# 1_esp32.net
KiCad netlist of a schematic drawn in Altium Designer
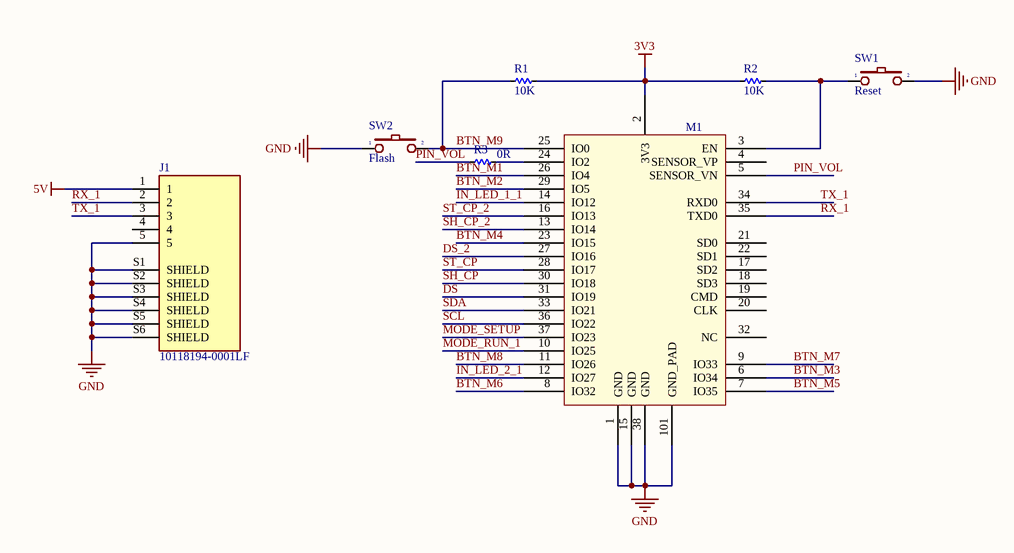
[diagram p0: [1]esp32.SchDoc]

(export (version "E")
  (design (tool "Eeschema 10.0.6"))
  (components
    (comp (ref "J1")
      (value "10118194-0001LF")
      (footprint "AMPHENOL_10118194-0001LF")
      (description "USB - micro B USB 2.0 Receptacle Connector 5 Position Surface Mount, Right Angle; Through Hole")
      (fields (field (name "MF") "Amphenol ICC"))
      (libsource (lib "10118194-0001LF") (part "10118194-0001LF"))
    )
    (comp (ref "M1")
      (value "ESP32S_Module")
      (footprint "ESP32S")
      (description "Esp-32S")
      (libsource (lib "ESP32S") (part "ESP32S_Module"))
    )
    (comp (ref "R1")
      (value "10K")
      (footprint "RES-SMD-0603")
      (description "Resistor")
      (fields
        (field (name "MANUFACTURER") "Generic Components")
        (field (name "PUBLISHER") "Altium Hobart Technology Centre")
      )
      (libsource (lib "LIBRARY") (part "Res-SMD"))
    )
    (comp (ref "R2")
      (value "10K")
      (footprint "RES-SMD-0603")
      (description "Resistor")
      (fields
        (field (name "MANUFACTURER") "Generic Components")
        (field (name "PUBLISHER") "Altium Hobart Technology Centre")
      )
      (libsource (lib "LIBRARY") (part "Res-SMD"))
    )
    (comp (ref "R3")
      (value "0R")
      (footprint "RES-SMD-0603")
      (description "Resistor")
      (fields
        (field (name "MANUFACTURER") "Generic Components")
        (field (name "PUBLISHER") "Altium Hobart Technology Centre")
      )
      (libsource (lib "LIBRARY") (part "Res-SMD"))
    )
    (comp (ref "SW1")
      (value "Reset")
      (footprint "SW1-SMD")
      (description "Switch button 2 pin")
      (libsource (lib "LIBRARY") (part "SW2"))
    )
    (comp (ref "SW2")
      (value "Flash")
      (footprint "SW-DIP1-1")
      (description "Switch button 2 pin")
      (libsource (lib "LIBRARY") (part "SW2"))
    )
  )
  (nets
    (net (code "1") (name "/BTN_M1") (class "Default")
      (node (ref "M1") (pin "26") (pinfunction "IO4_26") (pintype "passive"))
    )
    (net (code "2") (name "/BTN_M2") (class "Default")
      (node (ref "M1") (pin "29") (pinfunction "IO5_29") (pintype "passive"))
    )
    (net (code "3") (name "/BTN_M3") (class "Default")
      (node (ref "M1") (pin "6") (pinfunction "IO34_6") (pintype "passive"))
    )
    (net (code "4") (name "/BTN_M4") (class "Default")
      (node (ref "M1") (pin "23") (pinfunction "IO15_23") (pintype "passive"))
    )
    (net (code "5") (name "/BTN_M5") (class "Default")
      (node (ref "M1") (pin "7") (pinfunction "IO35_7") (pintype "passive"))
    )
    (net (code "6") (name "/BTN_M6") (class "Default")
      (node (ref "M1") (pin "8") (pinfunction "IO32_8") (pintype "passive"))
    )
    (net (code "7") (name "/BTN_M7") (class "Default")
      (node (ref "M1") (pin "9") (pinfunction "IO33_9") (pintype "passive"))
    )
    (net (code "8") (name "/BTN_M8") (class "Default")
      (node (ref "M1") (pin "11") (pinfunction "IO26_11") (pintype "passive"))
    )
    (net (code "9") (name "/BTN_M9") (class "Default")
      (node (ref "M1") (pin "25") (pinfunction "IO0_25") (pintype "passive"))
      (node (ref "R1") (pin "2") (pinfunction "2_2") (pintype "passive"))
      (node (ref "SW2") (pin "2") (pinfunction "2_2") (pintype "passive"))
    )
    (net (code "10") (name "/DS") (class "Default")
      (node (ref "M1") (pin "31") (pinfunction "IO19_31") (pintype "passive"))
    )
    (net (code "11") (name "/DS_2") (class "Default")
      (node (ref "M1") (pin "27") (pinfunction "IO16_27") (pintype "passive"))
    )
    (net (code "12") (name "/IN_LED_1_1") (class "Default")
      (node (ref "M1") (pin "14") (pinfunction "IO12_14") (pintype "passive"))
    )
    (net (code "13") (name "/IN_LED_2_1") (class "Default")
      (node (ref "M1") (pin "12") (pinfunction "IO27_12") (pintype "passive"))
    )
    (net (code "14") (name "/MODE_RUN_1") (class "Default")
      (node (ref "M1") (pin "10") (pinfunction "IO25_10") (pintype "passive"))
    )
    (net (code "15") (name "/MODE_SETUP") (class "Default")
      (node (ref "M1") (pin "37") (pinfunction "IO23_37") (pintype "passive"))
    )
    (net (code "16") (name "/PIN_VOL") (class "Default")
      (node (ref "M1") (pin "5") (pinfunction "SENSOR_VN_5") (pintype "passive"))
      (node (ref "R3") (pin "1") (pinfunction "1_1") (pintype "passive"))
    )
    (net (code "17") (name "/RX_1") (class "Default")
      (node (ref "J1") (pin "2") (pinfunction "2_2") (pintype "passive"))
      (node (ref "M1") (pin "35") (pinfunction "TXD0_35") (pintype "passive"))
    )
    (net (code "18") (name "/SCL") (class "Default")
      (node (ref "M1") (pin "36") (pinfunction "IO22_36") (pintype "passive"))
    )
    (net (code "19") (name "/SDA") (class "Default")
      (node (ref "M1") (pin "33") (pinfunction "IO21_33") (pintype "passive"))
    )
    (net (code "20") (name "/SH_CP") (class "Default")
      (node (ref "M1") (pin "30") (pinfunction "IO18_30") (pintype "passive"))
    )
    (net (code "21") (name "/SH_CP_2") (class "Default")
      (node (ref "M1") (pin "13") (pinfunction "IO14_13") (pintype "passive"))
    )
    (net (code "22") (name "/ST_CP") (class "Default")
      (node (ref "M1") (pin "28") (pinfunction "IO17_28") (pintype "passive"))
    )
    (net (code "23") (name "/ST_CP_2") (class "Default")
      (node (ref "M1") (pin "16") (pinfunction "IO13_16") (pintype "passive"))
    )
    (net (code "24") (name "/TX_1") (class "Default")
      (node (ref "J1") (pin "3") (pinfunction "3_3") (pintype "passive"))
      (node (ref "M1") (pin "34") (pinfunction "RXD0_34") (pintype "passive"))
    )
    (net (code "25") (name "3V3") (class "Default")
      (node (ref "M1") (pin "2") (pinfunction "3V3_2") (pintype "power_in"))
      (node (ref "R1") (pin "1") (pinfunction "1_1") (pintype "passive"))
      (node (ref "R2") (pin "2") (pinfunction "2_2") (pintype "passive"))
    )
    (net (code "26") (name "5V") (class "Default")
      (node (ref "J1") (pin "1") (pinfunction "1_1") (pintype "passive"))
    )
    (net (code "27") (name "GND") (class "Default")
      (node (ref "J1") (pin "5") (pinfunction "5_5") (pintype "passive"))
      (node (ref "J1") (pin "S1") (pinfunction "SHIELD_S1") (pintype "passive"))
      (node (ref "J1") (pin "S2") (pinfunction "SHIELD_S2") (pintype "passive"))
      (node (ref "J1") (pin "S3") (pinfunction "SHIELD_S3") (pintype "passive"))
      (node (ref "J1") (pin "S4") (pinfunction "SHIELD_S4") (pintype "passive"))
      (node (ref "J1") (pin "S5") (pinfunction "SHIELD_S5") (pintype "passive"))
      (node (ref "J1") (pin "S6") (pinfunction "SHIELD_S6") (pintype "passive"))
      (node (ref "M1") (pin "1") (pinfunction "GND_1") (pintype "power_in"))
      (node (ref "M1") (pin "101") (pinfunction "GND_PAD_101") (pintype "power_in"))
      (node (ref "M1") (pin "15") (pinfunction "GND_15") (pintype "power_in"))
      (node (ref "M1") (pin "38") (pinfunction "GND_38") (pintype "power_in"))
      (node (ref "SW1") (pin "2") (pinfunction "2_2") (pintype "passive"))
      (node (ref "SW2") (pin "1") (pinfunction "1_1") (pintype "passive"))
    )
    (net (code "28") (name "Net-(M1-EN)") (class "Default")
      (node (ref "M1") (pin "3") (pinfunction "EN_3") (pintype "power_in"))
      (node (ref "R2") (pin "1") (pinfunction "1_1") (pintype "passive"))
      (node (ref "SW1") (pin "1") (pinfunction "1_1") (pintype "passive"))
    )
    (net (code "29") (name "Net-(M1-IO2)") (class "Default")
      (node (ref "M1") (pin "24") (pinfunction "IO2_24") (pintype "passive"))
      (node (ref "R3") (pin "2") (pinfunction "2_2") (pintype "passive"))
    )
    (net (code "30") (name "unconnected-(J1-Pad4)") (class "Default")
      (node (ref "J1") (pin "4") (pinfunction "4_4") (pintype "passive"))
    )
    (net (code "31") (name "unconnected-(M1-CLK-Pad20)") (class "Default")
      (node (ref "M1") (pin "20") (pinfunction "CLK_20") (pintype "passive"))
    )
    (net (code "32") (name "unconnected-(M1-CMD-Pad19)") (class "Default")
      (node (ref "M1") (pin "19") (pinfunction "CMD_19") (pintype "passive"))
    )
    (net (code "33") (name "unconnected-(M1-NC-Pad32)") (class "Default")
      (node (ref "M1") (pin "32") (pinfunction "NC_32") (pintype "passive"))
    )
    (net (code "34") (name "unconnected-(M1-SD0-Pad21)") (class "Default")
      (node (ref "M1") (pin "21") (pinfunction "SD0_21") (pintype "passive"))
    )
    (net (code "35") (name "unconnected-(M1-SD1-Pad22)") (class "Default")
      (node (ref "M1") (pin "22") (pinfunction "SD1_22") (pintype "passive"))
    )
    (net (code "36") (name "unconnected-(M1-SD2-Pad17)") (class "Default")
      (node (ref "M1") (pin "17") (pinfunction "SD2_17") (pintype "passive"))
    )
    (net (code "37") (name "unconnected-(M1-SD3-Pad18)") (class "Default")
      (node (ref "M1") (pin "18") (pinfunction "SD3_18") (pintype "passive"))
    )
    (net (code "38") (name "unconnected-(M1-SENSOR_VP-Pad4)") (class "Default")
      (node (ref "M1") (pin "4") (pinfunction "SENSOR_VP_4") (pintype "passive"))
    )
  )
)
